# BKN-3.net
KiCad netlist of a schematic drawn in Altium Designer
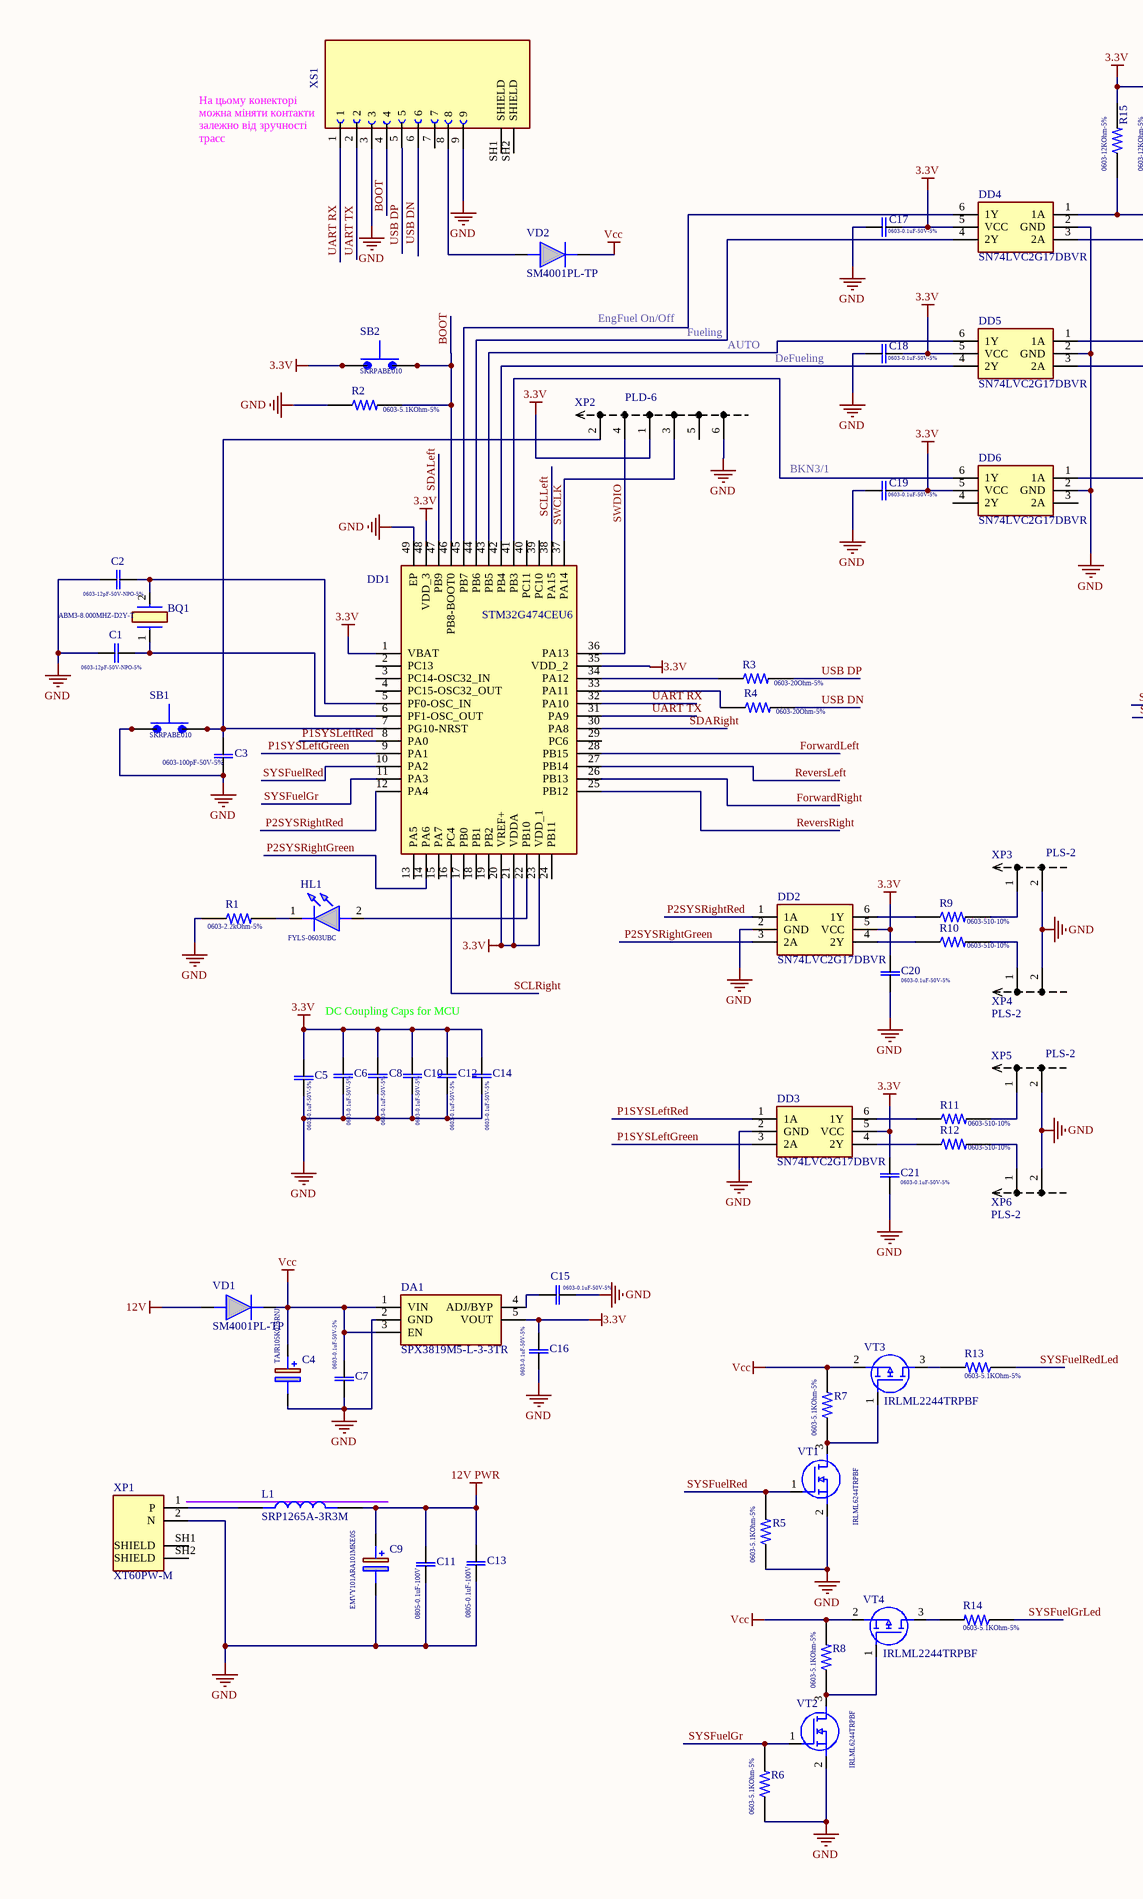
[diagram p0: BKN-3.SchDoc, left]
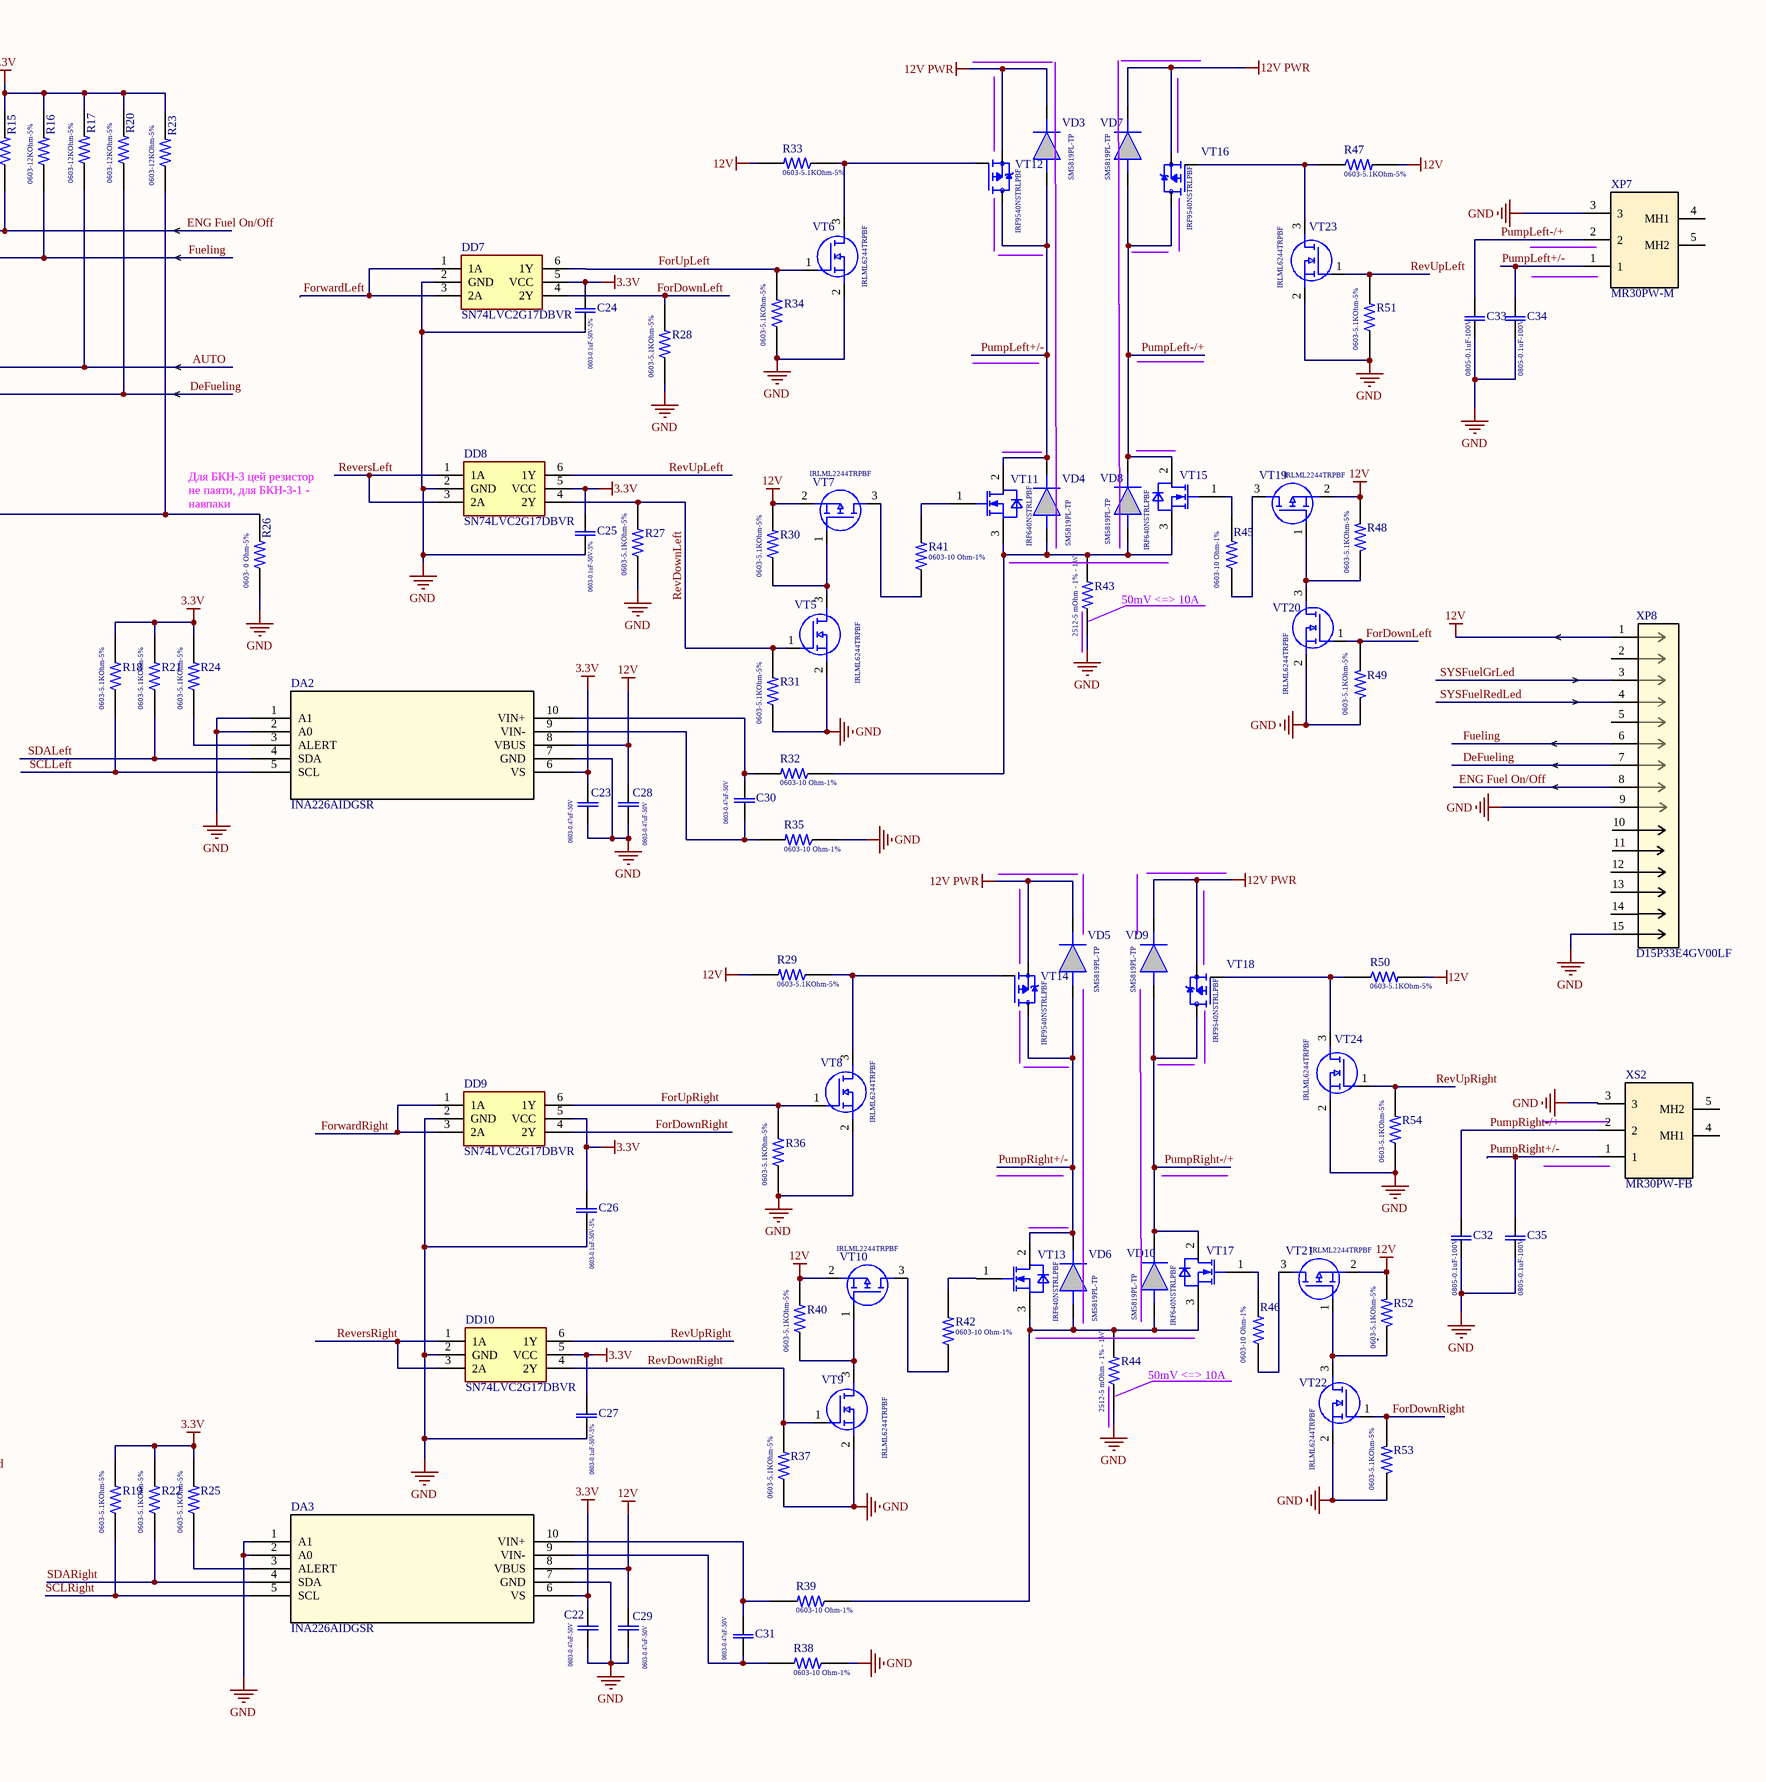
[diagram p1: BKN-3.SchDoc, right]

(export (version "E")
  (design (tool "Eeschema 10.0.6"))
  (components
    (comp (ref "BQ1")
      (value "ABM3-8.000MHZ-D2Y-T")
      (footprint "ABM3-25.000MHz")
      (description "ABM3-8.000MHZ-D2Y-T Кварцевий резонатор Космодром код товару: 00-00066552 Виробник:ABRACON")
      (libsource (lib "Quartz") (part "ABM3-25.000MHz"))
    )
    (comp (ref "C1")
      (value "0603-12pF-50V-NPO-5%")
      (footprint "C0603")
      (libsource (lib "Cap") (part "CAP0603"))
    )
    (comp (ref "C2")
      (value "0603-12pF-50V-NPO-5%")
      (footprint "C0603")
      (libsource (lib "Cap") (part "CAP0603"))
    )
    (comp (ref "C3") (value "0603-100pF-50V-5%") (footprint "C0603") (libsource (lib "Cap") (part "CAP0603")))
    (comp (ref "C4")
      (value "TAJR105K025RNJ")
      (footprint "TAJR105K025RNJ")
      (libsource (lib "CapElectrolite") (part "TAJR105K025RNJ"))
    )
    (comp (ref "C5") (value "0603-0.1uF-50V-5%") (footprint "C0603") (libsource (lib "Cap") (part "CAP0603")))
    (comp (ref "C6") (value "0603-0.1uF-50V-5%") (footprint "C0603") (libsource (lib "Cap") (part "CAP0603")))
    (comp (ref "C7") (value "0603-0.1uF-50V-5%") (footprint "C0603") (libsource (lib "Cap") (part "CAP0603")))
    (comp (ref "C8") (value "0603-0.1uF-50V-5%") (footprint "C0603") (libsource (lib "Cap") (part "CAP0603")))
    (comp (ref "C9")
      (value "EMVY101ARA101MKE0S")
      (footprint "EMVY101ARA101MKE0S")
      (libsource (lib "CapElectrolite") (part "EMVY101ARA101MKE0S"))
    )
    (comp (ref "C10")
      (value "0603-0.1uF-50V-5%")
      (footprint "C0603")
      (libsource (lib "Cap") (part "CAP0603"))
    )
    (comp (ref "C11")
      (value "0805-0.1uF-100V")
      (footprint "Cap0805")
      (libsource (lib "Cap") (part "Cap0805"))
    )
    (comp (ref "C12")
      (value "0603-0.1uF-50V-5%")
      (footprint "C0603")
      (libsource (lib "Cap") (part "CAP0603"))
    )
    (comp (ref "C13")
      (value "0805-0.1uF-100V")
      (footprint "Cap0805")
      (libsource (lib "Cap") (part "Cap0805"))
    )
    (comp (ref "C14")
      (value "0603-0.1uF-50V-5%")
      (footprint "C0603")
      (libsource (lib "Cap") (part "CAP0603"))
    )
    (comp (ref "C15")
      (value "0603-0.1uF-50V-5%")
      (footprint "C0603")
      (libsource (lib "Cap") (part "CAP0603"))
    )
    (comp (ref "C16")
      (value "0603-0.1uF-50V-5%")
      (footprint "C0603")
      (libsource (lib "Cap") (part "CAP0603"))
    )
    (comp (ref "C17")
      (value "0603-0.1uF-50V-5%")
      (footprint "C0603")
      (libsource (lib "Cap") (part "CAP0603"))
    )
    (comp (ref "C18")
      (value "0603-0.1uF-50V-5%")
      (footprint "C0603")
      (libsource (lib "Cap") (part "CAP0603"))
    )
    (comp (ref "C19")
      (value "0603-0.1uF-50V-5%")
      (footprint "C0603")
      (libsource (lib "Cap") (part "CAP0603"))
    )
    (comp (ref "C20")
      (value "0603-0.1uF-50V-5%")
      (footprint "C0603")
      (libsource (lib "Cap") (part "CAP0603"))
    )
    (comp (ref "C21")
      (value "0603-0.1uF-50V-5%")
      (footprint "C0603")
      (libsource (lib "Cap") (part "CAP0603"))
    )
    (comp (ref "C22") (value "0603-0.47uF-50V") (footprint "C0603") (libsource (lib "Cap") (part "CAP0603")))
    (comp (ref "C23") (value "0603-0.47uF-50V") (footprint "C0603") (libsource (lib "Cap") (part "CAP0603")))
    (comp (ref "C24")
      (value "0603-0.1uF-50V-5%")
      (footprint "C0603")
      (libsource (lib "Cap") (part "CAP0603"))
    )
    (comp (ref "C25")
      (value "0603-0.1uF-50V-5%")
      (footprint "C0603")
      (libsource (lib "Cap") (part "CAP0603"))
    )
    (comp (ref "C26")
      (value "0603-0.1uF-50V-5%")
      (footprint "C0603")
      (libsource (lib "Cap") (part "CAP0603"))
    )
    (comp (ref "C27")
      (value "0603-0.1uF-50V-5%")
      (footprint "C0603")
      (libsource (lib "Cap") (part "CAP0603"))
    )
    (comp (ref "C28") (value "0603-0.47uF-50V") (footprint "C0603") (libsource (lib "Cap") (part "CAP0603")))
    (comp (ref "C29") (value "0603-0.47uF-50V") (footprint "C0603") (libsource (lib "Cap") (part "CAP0603")))
    (comp (ref "C30") (value "0603-0.47uF-50V") (footprint "C0603") (libsource (lib "Cap") (part "CAP0603")))
    (comp (ref "C31") (value "0603-0.47uF-50V") (footprint "C0603") (libsource (lib "Cap") (part "CAP0603")))
    (comp (ref "C32")
      (value "0805-0.1uF-100V")
      (footprint "Cap0805")
      (libsource (lib "Cap") (part "Cap0805"))
    )
    (comp (ref "C33")
      (value "0805-0.1uF-100V")
      (footprint "Cap0805")
      (libsource (lib "Cap") (part "Cap0805"))
    )
    (comp (ref "C34")
      (value "0805-0.1uF-100V")
      (footprint "Cap0805")
      (libsource (lib "Cap") (part "Cap0805"))
    )
    (comp (ref "C35")
      (value "0805-0.1uF-100V")
      (footprint "Cap0805")
      (libsource (lib "Cap") (part "Cap0805"))
    )
    (comp (ref "DA1")
      (value "SPX3819M5-L-3-3TR")
      (footprint "SOT95P280x145-5N")
      (libsource (lib "LDO") (part "SPX3819M5-L-3-3TR"))
    )
    (comp (ref "DA2")
      (value "INA226AIDGSR")
      (footprint "INA226AIDGSR")
      (libsource (lib "CurrentMonitor") (part "INA226AIDGSR"))
    )
    (comp (ref "DA3")
      (value "INA226AIDGSR")
      (footprint "INA226AIDGSR")
      (libsource (lib "CurrentMonitor") (part "INA226AIDGSR"))
    )
    (comp (ref "DD1")
      (value "STM32G474CEU6")
      (footprint "QFN50P700X700X60-49N-D")
      (description "STM32G474CEU6\r\nВиробник:\r\nSTMicroelectronics\r\nIC MCU 32BIT 512KB FLSH 48UFQFPN VD MAIS")
      (libsource (lib "STM Controllers") (part "STM32G474CEU6"))
    )
    (comp (ref "DD2")
      (value "SN74LVC2G17DBVR")
      (footprint "SOT95P280x145-6N")
      (libsource (lib "") (part "SN74LVC2G17DBVR_1"))
    )
    (comp (ref "DD3")
      (value "SN74LVC2G17DBVR")
      (footprint "SOT95P280x145-6N")
      (libsource (lib "") (part "SN74LVC2G17DBVR_1"))
    )
    (comp (ref "DD4")
      (value "SN74LVC2G17DBVR")
      (footprint "SOT95P280x145-6N")
      (libsource (lib "Buffer") (part "SN74LVC2G17DBVR"))
    )
    (comp (ref "DD5")
      (value "SN74LVC2G17DBVR")
      (footprint "SOT95P280x145-6N")
      (libsource (lib "Buffer") (part "SN74LVC2G17DBVR"))
    )
    (comp (ref "DD6")
      (value "SN74LVC2G17DBVR")
      (footprint "SOT95P280x145-6N")
      (libsource (lib "Buffer") (part "SN74LVC2G17DBVR"))
    )
    (comp (ref "DD7")
      (value "SN74LVC2G17DBVR")
      (footprint "SOT95P280x145-6N")
      (libsource (lib "") (part "SN74LVC2G17DBVR_1"))
    )
    (comp (ref "DD8")
      (value "SN74LVC2G17DBVR")
      (footprint "SOT95P280x145-6N")
      (libsource (lib "") (part "SN74LVC2G17DBVR_1"))
    )
    (comp (ref "DD9")
      (value "SN74LVC2G17DBVR")
      (footprint "SOT95P280x145-6N")
      (libsource (lib "") (part "SN74LVC2G17DBVR_1"))
    )
    (comp (ref "DD10")
      (value "SN74LVC2G17DBVR")
      (footprint "SOT95P280x145-6N")
      (libsource (lib "") (part "SN74LVC2G17DBVR_1"))
    )
    (comp (ref "HL1") (value "FYLS-0603UBC") (footprint "LED0603") (libsource (lib "LEDs") (part "LED0603")))
    (comp (ref "L1")
      (value "SRP1265A-3R3M")
      (footprint "SRP1265A-3R3M")
      (libsource (lib "Inductance") (part "SRP1265A-3R3M"))
    )
    (comp (ref "R1")
      (value "0603-2.2kOhm-5%")
      (footprint "Res0603")
      (libsource (lib "Resisitor") (part "Res0603"))
    )
    (comp (ref "R2")
      (value "0603-5.1KOhm-5%")
      (footprint "Res0603")
      (libsource (lib "Resisitor") (part "Res0603"))
    )
    (comp (ref "R3")
      (value "0603-20Ohm-5%")
      (footprint "Res0603")
      (libsource (lib "Resisitor") (part "Res0603"))
    )
    (comp (ref "R4")
      (value "0603-20Ohm-5%")
      (footprint "Res0603")
      (libsource (lib "Resisitor") (part "Res0603"))
    )
    (comp (ref "R5")
      (value "0603-5.1KOhm-5%")
      (footprint "Res0603")
      (libsource (lib "Resisitor") (part "Res0603"))
    )
    (comp (ref "R6")
      (value "0603-5.1KOhm-5%")
      (footprint "Res0603")
      (libsource (lib "Resisitor") (part "Res0603"))
    )
    (comp (ref "R7")
      (value "0603-5.1KOhm-5%")
      (footprint "Res0603")
      (libsource (lib "Resisitor") (part "Res0603"))
    )
    (comp (ref "R8")
      (value "0603-5.1KOhm-5%")
      (footprint "Res0603")
      (libsource (lib "Resisitor") (part "Res0603"))
    )
    (comp (ref "R9")
      (value "0603-510-10%")
      (footprint "Res0603")
      (libsource (lib "Resisitor") (part "Res0603"))
    )
    (comp (ref "R10")
      (value "0603-510-10%")
      (footprint "Res0603")
      (libsource (lib "Resisitor") (part "Res0603"))
    )
    (comp (ref "R11")
      (value "0603-510-10%")
      (footprint "Res0603")
      (libsource (lib "Resisitor") (part "Res0603"))
    )
    (comp (ref "R12")
      (value "0603-510-10%")
      (footprint "Res0603")
      (libsource (lib "Resisitor") (part "Res0603"))
    )
    (comp (ref "R13")
      (value "0603-5.1KOhm-5%")
      (footprint "Res0603")
      (libsource (lib "Resisitor") (part "Res0603"))
    )
    (comp (ref "R14")
      (value "0603-5.1KOhm-5%")
      (footprint "Res0603")
      (libsource (lib "Resisitor") (part "Res0603"))
    )
    (comp (ref "R15")
      (value "0603-12KOhm-5%")
      (footprint "Res0603")
      (libsource (lib "Resisitor") (part "Res0603"))
    )
    (comp (ref "R16")
      (value "0603-12KOhm-5%")
      (footprint "Res0603")
      (libsource (lib "Resisitor") (part "Res0603"))
    )
    (comp (ref "R17")
      (value "0603-12KOhm-5%")
      (footprint "Res0603")
      (libsource (lib "Resisitor") (part "Res0603"))
    )
    (comp (ref "R18")
      (value "0603-5.1KOhm-5%")
      (footprint "Res0603")
      (libsource (lib "Resisitor") (part "Res0603"))
    )
    (comp (ref "R19")
      (value "0603-5.1KOhm-5%")
      (footprint "Res0603")
      (libsource (lib "Resisitor") (part "Res0603"))
    )
    (comp (ref "R20")
      (value "0603-12KOhm-5%")
      (footprint "Res0603")
      (libsource (lib "Resisitor") (part "Res0603"))
    )
    (comp (ref "R21")
      (value "0603-5.1KOhm-5%")
      (footprint "Res0603")
      (libsource (lib "Resisitor") (part "Res0603"))
    )
    (comp (ref "R22")
      (value "0603-5.1KOhm-5%")
      (footprint "Res0603")
      (libsource (lib "Resisitor") (part "Res0603"))
    )
    (comp (ref "R23")
      (value "0603-12KOhm-5%")
      (footprint "Res0603")
      (libsource (lib "Resisitor") (part "Res0603"))
    )
    (comp (ref "R24")
      (value "0603-5.1KOhm-5%")
      (footprint "Res0603")
      (libsource (lib "Resisitor") (part "Res0603"))
    )
    (comp (ref "R25")
      (value "0603-5.1KOhm-5%")
      (footprint "Res0603")
      (libsource (lib "Resisitor") (part "Res0603"))
    )
    (comp (ref "R26")
      (value "0603- 0 Ohm-5%")
      (footprint "Res0603")
      (libsource (lib "Resisitor") (part "Res0603"))
    )
    (comp (ref "R27")
      (value "0603-5.1KOhm-5%")
      (footprint "Res0603")
      (libsource (lib "Resisitor") (part "Res0603"))
    )
    (comp (ref "R28")
      (value "0603-5.1KOhm-5%")
      (footprint "Res0603")
      (libsource (lib "Resisitor") (part "Res0603"))
    )
    (comp (ref "R29")
      (value "0603-5.1KOhm-5%")
      (footprint "Res0603")
      (libsource (lib "Resisitor") (part "Res0603"))
    )
    (comp (ref "R30")
      (value "0603-5.1KOhm-5%")
      (footprint "Res0603")
      (libsource (lib "Resisitor") (part "Res0603"))
    )
    (comp (ref "R31")
      (value "0603-5.1KOhm-5%")
      (footprint "Res0603")
      (libsource (lib "Resisitor") (part "Res0603"))
    )
    (comp (ref "R32")
      (value "0603-10 Ohm-1%")
      (footprint "Res0603")
      (libsource (lib "Resisitor") (part "Res0603"))
    )
    (comp (ref "R33")
      (value "0603-5.1KOhm-5%")
      (footprint "Res0603")
      (libsource (lib "Resisitor") (part "Res0603"))
    )
    (comp (ref "R34")
      (value "0603-5.1KOhm-5%")
      (footprint "Res0603")
      (libsource (lib "Resisitor") (part "Res0603"))
    )
    (comp (ref "R35")
      (value "0603-10 Ohm-1%")
      (footprint "Res0603")
      (libsource (lib "Resisitor") (part "Res0603"))
    )
    (comp (ref "R36")
      (value "0603-5.1KOhm-5%")
      (footprint "Res0603")
      (libsource (lib "Resisitor") (part "Res0603"))
    )
    (comp (ref "R37")
      (value "0603-5.1KOhm-5%")
      (footprint "Res0603")
      (libsource (lib "Resisitor") (part "Res0603"))
    )
    (comp (ref "R38")
      (value "0603-10 Ohm-1%")
      (footprint "Res0603")
      (libsource (lib "Resisitor") (part "Res0603"))
    )
    (comp (ref "R39")
      (value "0603-10 Ohm-1%")
      (footprint "Res0603")
      (libsource (lib "Resisitor") (part "Res0603"))
    )
    (comp (ref "R40")
      (value "0603-5.1KOhm-5%")
      (footprint "Res0603")
      (libsource (lib "Resisitor") (part "Res0603"))
    )
    (comp (ref "R41")
      (value "0603-10 Ohm-1%")
      (footprint "Res0603")
      (libsource (lib "Resisitor") (part "Res0603"))
    )
    (comp (ref "R42")
      (value "0603-10 Ohm-1%")
      (footprint "Res0603")
      (libsource (lib "Resisitor") (part "Res0603"))
    )
    (comp (ref "R43")
      (value "2512-5 mOhm - 1% - 1W")
      (footprint "Res2512")
      (libsource (lib "Resisitor") (part "Res2512"))
    )
    (comp (ref "R44")
      (value "2512-5 mOhm - 1% - 1W")
      (footprint "Res2512")
      (libsource (lib "Resisitor") (part "Res2512"))
    )
    (comp (ref "R45")
      (value "0603-10 Ohm-1%")
      (footprint "Res0603")
      (libsource (lib "Resisitor") (part "Res0603"))
    )
    (comp (ref "R46")
      (value "0603-10 Ohm-1%")
      (footprint "Res0603")
      (libsource (lib "Resisitor") (part "Res0603"))
    )
    (comp (ref "R47")
      (value "0603-5.1KOhm-5%")
      (footprint "Res0603")
      (libsource (lib "Resisitor") (part "Res0603"))
    )
    (comp (ref "R48")
      (value "0603-5.1KOhm-5%")
      (footprint "Res0603")
      (libsource (lib "Resisitor") (part "Res0603"))
    )
    (comp (ref "R49")
      (value "0603-5.1KOhm-5%")
      (footprint "Res0603")
      (libsource (lib "Resisitor") (part "Res0603"))
    )
    (comp (ref "R50")
      (value "0603-5.1KOhm-5%")
      (footprint "Res0603")
      (libsource (lib "Resisitor") (part "Res0603"))
    )
    (comp (ref "R51")
      (value "0603-5.1KOhm-5%")
      (footprint "Res0603")
      (libsource (lib "Resisitor") (part "Res0603"))
    )
    (comp (ref "R52")
      (value "0603-5.1KOhm-5%")
      (footprint "Res0603")
      (libsource (lib "Resisitor") (part "Res0603"))
    )
    (comp (ref "R53")
      (value "0603-5.1KOhm-5%")
      (footprint "Res0603")
      (libsource (lib "Resisitor") (part "Res0603"))
    )
    (comp (ref "R54")
      (value "0603-5.1KOhm-5%")
      (footprint "Res0603")
      (libsource (lib "Resisitor") (part "Res0603"))
    )
    (comp (ref "SB1")
      (value "SKRPABE010")
      (footprint "SKRPABE010")
      (libsource (lib "Button") (part "SKRPABE010"))
    )
    (comp (ref "SB2")
      (value "SKRPABE010")
      (footprint "SKRPABE010")
      (libsource (lib "Button") (part "SKRPABE010"))
    )
    (comp (ref "VD1")
      (value "SM4001PL-TP")
      (footprint "SODFL3716X120N")
      (description "Производитель: MCC\r\nТип корпуса: SOD-123\r\nКосмодром код товара: 00-00072425")
      (libsource (lib "Diodes") (part "SM4001PL-TP"))
    )
    (comp (ref "VD2")
      (value "SM4001PL-TP")
      (footprint "SODFL3716X120N")
      (libsource (lib "Diodes") (part "SM4001PL-TP"))
    )
    (comp (ref "VD3")
      (value "SM5819PL-TP")
      (footprint "SM5819PL-TP (SOD123)")
      (description "SM5819PL\r\nImrad Артикул: 195754\r\nПроизводитель: MCC\r\nКорпус: SOD-123")
      (libsource (lib "Diodes") (part "SM5819PL-TP"))
    )
    (comp (ref "VD4")
      (value "SM5819PL-TP")
      (footprint "SM5819PL-TP (SOD123)")
      (description "SM5819PL\r\nImrad Артикул: 195754\r\nПроизводитель: MCC\r\nКорпус: SOD-123")
      (libsource (lib "Diodes") (part "SM5819PL-TP"))
    )
    (comp (ref "VD5")
      (value "SM5819PL-TP")
      (footprint "SM5819PL-TP (SOD123)")
      (description "SM5819PL\r\nImrad Артикул: 195754\r\nПроизводитель: MCC\r\nКорпус: SOD-123")
      (libsource (lib "Diodes") (part "SM5819PL-TP"))
    )
    (comp (ref "VD6")
      (value "SM5819PL-TP")
      (footprint "SM5819PL-TP (SOD123)")
      (description "SM5819PL\r\nImrad Артикул: 195754\r\nПроизводитель: MCC\r\nКорпус: SOD-123")
      (libsource (lib "Diodes") (part "SM5819PL-TP"))
    )
    (comp (ref "VD7")
      (value "SM5819PL-TP")
      (footprint "SM5819PL-TP (SOD123)")
      (description "SM5819PL\r\nImrad Артикул: 195754\r\nПроизводитель: MCC\r\nКорпус: SOD-123")
      (libsource (lib "Diodes") (part "SM5819PL-TP"))
    )
    (comp (ref "VD8")
      (value "SM5819PL-TP")
      (footprint "SM5819PL-TP (SOD123)")
      (description "SM5819PL\r\nImrad Артикул: 195754\r\nПроизводитель: MCC\r\nКорпус: SOD-123")
      (libsource (lib "Diodes") (part "SM5819PL-TP"))
    )
    (comp (ref "VD9")
      (value "SM5819PL-TP")
      (footprint "SM5819PL-TP (SOD123)")
      (description "SM5819PL\r\nImrad Артикул: 195754\r\nПроизводитель: MCC\r\nКорпус: SOD-123")
      (libsource (lib "Diodes") (part "SM5819PL-TP"))
    )
    (comp (ref "VD10")
      (value "SM5819PL-TP")
      (footprint "SM5819PL-TP (SOD123)")
      (description "SM5819PL\r\nImrad Артикул: 195754\r\nПроизводитель: MCC\r\nКорпус: SOD-123")
      (libsource (lib "Diodes") (part "SM5819PL-TP"))
    )
    (comp (ref "VT1")
      (value "IRLML6244TRPBF")
      (footprint "SOT95P230x110-3N")
      (libsource (lib "NFET") (part "IRLML6244"))
    )
    (comp (ref "VT2")
      (value "IRLML6244TRPBF")
      (footprint "SOT95P230x110-3N")
      (libsource (lib "NFET") (part "IRLML6244"))
    )
    (comp (ref "VT3")
      (value "IRLML2244TRPBF")
      (footprint "SOT95P237x112-3N")
      (libsource (lib "PFET") (part "IRLML2244"))
    )
    (comp (ref "VT4")
      (value "IRLML2244TRPBF")
      (footprint "SOT95P237x112-3N")
      (libsource (lib "PFET") (part "IRLML2244"))
    )
    (comp (ref "VT5")
      (value "IRLML6244TRPBF")
      (footprint "SOT95P230x110-3N")
      (libsource (lib "NFET") (part "IRLML6244"))
    )
    (comp (ref "VT6")
      (value "IRLML6244TRPBF")
      (footprint "SOT95P230x110-3N")
      (libsource (lib "NFET") (part "IRLML6244"))
    )
    (comp (ref "VT7")
      (value "IRLML2244TRPBF")
      (footprint "SOT95P237x112-3N")
      (libsource (lib "PFET") (part "IRLML2244"))
    )
    (comp (ref "VT8")
      (value "IRLML6244TRPBF")
      (footprint "SOT95P230x110-3N")
      (libsource (lib "NFET") (part "IRLML6244"))
    )
    (comp (ref "VT9")
      (value "IRLML6244TRPBF")
      (footprint "SOT95P230x110-3N")
      (libsource (lib "NFET") (part "IRLML6244"))
    )
    (comp (ref "VT10")
      (value "IRLML2244TRPBF")
      (footprint "SOT95P237x112-3N")
      (libsource (lib "PFET") (part "IRLML2244"))
    )
    (comp (ref "VT11")
      (value "IRF640NSTRLPBF")
      (footprint "IRF640NSTRLPBF")
      (libsource (lib "NFET") (part "IRF640NSTRLPBF"))
    )
    (comp (ref "VT12")
      (value "IRF9540NSTRLPBF")
      (footprint "IRF9540NSTRLPBF")
      (libsource (lib "PFET") (part "IRF9540NSTRLPBF"))
    )
    (comp (ref "VT13")
      (value "IRF640NSTRLPBF")
      (footprint "IRF640NSTRLPBF")
      (libsource (lib "NFET") (part "IRF640NSTRLPBF"))
    )
    (comp (ref "VT14")
      (value "IRF9540NSTRLPBF")
      (footprint "IRF9540NSTRLPBF")
      (libsource (lib "PFET") (part "IRF9540NSTRLPBF"))
    )
    (comp (ref "VT15")
      (value "IRF640NSTRLPBF")
      (footprint "IRF640NSTRLPBF")
      (libsource (lib "NFET") (part "IRF640NSTRLPBF"))
    )
    (comp (ref "VT16")
      (value "IRF9540NSTRLPBF")
      (footprint "IRF9540NSTRLPBF")
      (libsource (lib "PFET") (part "IRF9540NSTRLPBF"))
    )
    (comp (ref "VT17")
      (value "IRF640NSTRLPBF")
      (footprint "IRF640NSTRLPBF")
      (libsource (lib "NFET") (part "IRF640NSTRLPBF"))
    )
    (comp (ref "VT18")
      (value "IRF9540NSTRLPBF")
      (footprint "IRF9540NSTRLPBF")
      (libsource (lib "PFET") (part "IRF9540NSTRLPBF"))
    )
    (comp (ref "VT19")
      (value "IRLML2244TRPBF")
      (footprint "SOT95P237x112-3N")
      (libsource (lib "PFET") (part "IRLML2244"))
    )
    (comp (ref "VT20")
      (value "IRLML6244TRPBF")
      (footprint "SOT95P230x110-3N")
      (libsource (lib "NFET") (part "IRLML6244"))
    )
    (comp (ref "VT21")
      (value "IRLML2244TRPBF")
      (footprint "SOT95P237x112-3N")
      (libsource (lib "PFET") (part "IRLML2244"))
    )
    (comp (ref "VT22")
      (value "IRLML6244TRPBF")
      (footprint "SOT95P230x110-3N")
      (libsource (lib "NFET") (part "IRLML6244"))
    )
    (comp (ref "VT23")
      (value "IRLML6244TRPBF")
      (footprint "SOT95P230x110-3N")
      (libsource (lib "NFET") (part "IRLML6244"))
    )
    (comp (ref "VT24")
      (value "IRLML6244TRPBF")
      (footprint "SOT95P230x110-3N")
      (libsource (lib "NFET") (part "IRLML6244"))
    )
    (comp (ref "XP1") (value "XT60PW-M") (footprint "XT60PW-M") (libsource (lib "AMASS") (part "XT60PW-M")))
    (comp (ref "XP2") (value "PLD-6") (footprint "PLD-6") (libsource (lib "PLS_PLD") (part "PLD-6")))
    (comp (ref "XP3") (value "PLS-2") (footprint "PLS-2") (libsource (lib "PLS_PLD") (part "PLS-2")))
    (comp (ref "XP4") (value "PLS-2") (footprint "PLS-2") (libsource (lib "PLS_PLD") (part "PLS-2")))
    (comp (ref "XP5") (value "PLS-2") (footprint "PLS-2") (libsource (lib "PLS_PLD") (part "PLS-2")))
    (comp (ref "XP6") (value "PLS-2") (footprint "PLS-2") (libsource (lib "PLS_PLD") (part "PLS-2")))
    (comp (ref "XP7")
      (value "MR30PW-M")
      (footprint "MR30PW-M")
      (description "MR30PW-M\r\nImrad Артикул: 393200\r\nВиробник: AMASS\r\nНаявність: В наявності")
      (libsource (lib "AMASS") (part "MR30PW-M"))
    )
    (comp (ref "XP8")
      (value "D15P33E4GV00LF")
      (footprint "D15P33E4GV00LF (Amphenol)")
      (description "DRB-15MA\r\nImrad Артикул: 201593\r\nНазва виробника: DS1037-15MNAKT74-0CC\r\nВиробник: CONNFLY")
      (libsource (lib "DSUB") (part "D15P33E4GV00LF"))
    )
    (comp (ref "XS1")
      (value "AMPHENOL_LD09S33E4GV00LF (DB9 ThrHole Right Receptacle )")
      (footprint "AMPHENOL_LD09S33E4GV00LF (9pin receptacle)")
      (libsource (lib "DSUB") (part "AMPHENOL_LD09S33E4GV00LF (DB9 ThrHole Right Receptacle )"))
    )
    (comp (ref "XS2")
      (value "MR30PW-FB")
      (footprint "MR30PW-FB")
      (description "MR30PW-FB\r\nImrad Артикул: 393199\r\nВиробник: AMASS\r\nНаявність: В наявності")
      (libsource (lib "AMASS") (part "MR30PW-FB"))
    )
  )
  (nets
    (net (code "1") (name "/AUTO") (class "Default")
      (node (ref "DD5") (pin "1") (pinfunction "1A_1") (pintype "passive"))
      (node (ref "R17") (pin "1") (pinfunction "1_1") (pintype "passive"))
    )
    (net (code "2") (name "/BOOT") (class "Default")
      (node (ref "DD1") (pin "46") (pinfunction "PB8-BOOT0_46") (pintype "passive"))
      (node (ref "R2") (pin "2") (pinfunction "2_2") (pintype "passive"))
      (node (ref "SB2") (pin "3") (pinfunction "2_3") (pintype "passive"))
      (node (ref "SB2") (pin "4") (pinfunction "2_4") (pintype "passive"))
      (node (ref "XS1") (pin "4") (pinfunction "4_4") (pintype "passive"))
    )
    (net (code "3") (name "/DeFueling") (class "Default")
      (node (ref "DD5") (pin "3") (pinfunction "2A_3") (pintype "passive"))
      (node (ref "R20") (pin "1") (pinfunction "1_1") (pintype "passive"))
      (node (ref "XP8") (pin "7") (pinfunction "7_7") (pintype "passive"))
    )
    (net (code "4") (name "/ENG Fuel On{slash}Off") (class "Default")
      (node (ref "DD4") (pin "1") (pinfunction "1A_1") (pintype "passive"))
      (node (ref "R15") (pin "1") (pinfunction "1_1") (pintype "passive"))
      (node (ref "XP8") (pin "8") (pinfunction "8_8") (pintype "passive"))
    )
    (net (code "5") (name "/ForDownLeft") (class "Default")
      (node (ref "DD7") (pin "4") (pinfunction "2Y_4") (pintype "passive"))
      (node (ref "R28") (pin "2") (pinfunction "2_2") (pintype "passive"))
      (node (ref "R49") (pin "2") (pinfunction "2_2") (pintype "passive"))
      (node (ref "VT20") (pin "1") (pinfunction "G_1") (pintype "passive"))
    )
    (net (code "6") (name "/ForDownRight") (class "Default")
      (node (ref "DD9") (pin "4") (pinfunction "2Y_4") (pintype "passive"))
      (node (ref "R53") (pin "2") (pinfunction "2_2") (pintype "passive"))
      (node (ref "VT22") (pin "1") (pinfunction "G_1") (pintype "passive"))
    )
    (net (code "8") (name "/ForUpLeft") (class "Default")
      (node (ref "DD7") (pin "6") (pinfunction "1Y_6") (pintype "passive"))
      (node (ref "R34") (pin "2") (pinfunction "2_2") (pintype "passive"))
      (node (ref "VT6") (pin "1") (pinfunction "G_1") (pintype "passive"))
    )
    (net (code "9") (name "/ForUpRight") (class "Default")
      (node (ref "DD9") (pin "6") (pinfunction "1Y_6") (pintype "passive"))
      (node (ref "R36") (pin "2") (pinfunction "2_2") (pintype "passive"))
      (node (ref "VT8") (pin "1") (pinfunction "G_1") (pintype "passive"))
    )
    (net (code "10") (name "/ForwardLeft") (class "Default")
      (node (ref "DD1") (pin "28") (pinfunction "PB15_28") (pintype "passive"))
      (node (ref "DD7") (pin "1") (pinfunction "1A_1") (pintype "passive"))
      (node (ref "DD7") (pin "3") (pinfunction "2A_3") (pintype "passive"))
    )
    (net (code "11") (name "/ForwardRight") (class "Default")
      (node (ref "DD1") (pin "26") (pinfunction "PB13_26") (pintype "passive"))
      (node (ref "DD9") (pin "1") (pinfunction "1A_1") (pintype "passive"))
      (node (ref "DD9") (pin "3") (pinfunction "2A_3") (pintype "passive"))
    )
    (net (code "12") (name "/Fueling") (class "Default")
      (node (ref "DD4") (pin "3") (pinfunction "2A_3") (pintype "passive"))
      (node (ref "R16") (pin "1") (pinfunction "1_1") (pintype "passive"))
      (node (ref "XP8") (pin "6") (pinfunction "6_6") (pintype "passive"))
    )
    (net (code "13") (name "/P1SYSLeftGreen") (class "Default")
      (node (ref "DD1") (pin "9") (pinfunction "PA1_9") (pintype "passive"))
      (node (ref "DD3") (pin "3") (pinfunction "2A_3") (pintype "passive"))
    )
    (net (code "14") (name "/P1SYSLeftRed") (class "Default")
      (node (ref "DD1") (pin "8") (pinfunction "PA0_8") (pintype "passive"))
      (node (ref "DD3") (pin "1") (pinfunction "1A_1") (pintype "passive"))
    )
    (net (code "15") (name "/P2SYSRightGreen") (class "Default")
      (node (ref "DD1") (pin "14") (pinfunction "PA6_14") (pintype "passive"))
      (node (ref "DD2") (pin "3") (pinfunction "2A_3") (pintype "passive"))
    )
    (net (code "16") (name "/P2SYSRightRed") (class "Default")
      (node (ref "DD1") (pin "12") (pinfunction "PA4_12") (pintype "passive"))
      (node (ref "DD2") (pin "1") (pinfunction "1A_1") (pintype "passive"))
    )
    (net (code "17") (name "/PumpLeft+{slash}-") (class "Default")
      (node (ref "C34") (pin "1") (pinfunction "1_1") (pintype "passive"))
      (node (ref "VD3") (pin "2") (pinfunction "A_2") (pintype "passive"))
      (node (ref "VD4") (pin "1") (pinfunction "K_1") (pintype "passive"))
      (node (ref "VT11") (pin "2") (pinfunction "2,4_2") (pintype "passive"))
      (node (ref "VT12") (pin "4") (pinfunction "D_4") (pintype "passive"))
      (node (ref "XP7") (pin "1") (pinfunction "1_1") (pintype "passive"))
    )
    (net (code "18") (name "/PumpLeft-{slash}+") (class "Default")
      (node (ref "C33") (pin "1") (pinfunction "1_1") (pintype "passive"))
      (node (ref "VD7") (pin "2") (pinfunction "A_2") (pintype "passive"))
      (node (ref "VD8") (pin "1") (pinfunction "K_1") (pintype "passive"))
      (node (ref "VT15") (pin "2") (pinfunction "2,4_2") (pintype "passive"))
      (node (ref "VT16") (pin "4") (pinfunction "D_4") (pintype "passive"))
      (node (ref "XP7") (pin "2") (pinfunction "2_2") (pintype "passive"))
    )
    (net (code "19") (name "/PumpRight+{slash}-") (class "Default")
      (node (ref "C35") (pin "1") (pinfunction "1_1") (pintype "passive"))
      (node (ref "VD5") (pin "2") (pinfunction "A_2") (pintype "passive"))
      (node (ref "VD6") (pin "1") (pinfunction "K_1") (pintype "passive"))
      (node (ref "VT13") (pin "2") (pinfunction "2,4_2") (pintype "passive"))
      (node (ref "VT14") (pin "4") (pinfunction "D_4") (pintype "passive"))
      (node (ref "XS2") (pin "1") (pinfunction "1_1") (pintype "passive"))
    )
    (net (code "20") (name "/PumpRight-{slash}+") (class "Default")
      (node (ref "C32") (pin "1") (pinfunction "1_1") (pintype "passive"))
      (node (ref "VD10") (pin "1") (pinfunction "K_1") (pintype "passive"))
      (node (ref "VD9") (pin "2") (pinfunction "A_2") (pintype "passive"))
      (node (ref "VT17") (pin "2") (pinfunction "2,4_2") (pintype "passive"))
      (node (ref "VT18") (pin "4") (pinfunction "D_4") (pintype "passive"))
      (node (ref "XS2") (pin "2") (pinfunction "2_2") (pintype "passive"))
    )
    (net (code "21") (name "/RevDownLeft") (class "Default")
      (node (ref "DD8") (pin "4") (pinfunction "2Y_4") (pintype "passive"))
      (node (ref "R27") (pin "2") (pinfunction "2_2") (pintype "passive"))
      (node (ref "R31") (pin "2") (pinfunction "2_2") (pintype "passive"))
      (node (ref "VT5") (pin "1") (pinfunction "G_1") (pintype "passive"))
    )
    (net (code "22") (name "/RevDownRight") (class "Default")
      (node (ref "DD10") (pin "4") (pinfunction "2Y_4") (pintype "passive"))
      (node (ref "R37") (pin "2") (pinfunction "2_2") (pintype "passive"))
      (node (ref "VT9") (pin "1") (pinfunction "G_1") (pintype "passive"))
    )
    (net (code "23") (name "/RevUpLeft") (class "Default")
      (node (ref "DD8") (pin "6") (pinfunction "1Y_6") (pintype "passive"))
      (node (ref "R51") (pin "2") (pinfunction "2_2") (pintype "passive"))
      (node (ref "VT23") (pin "1") (pinfunction "G_1") (pintype "passive"))
    )
    (net (code "24") (name "/RevUpRight") (class "Default")
      (node (ref "DD10") (pin "6") (pinfunction "1Y_6") (pintype "passive"))
      (node (ref "R54") (pin "2") (pinfunction "2_2") (pintype "passive"))
      (node (ref "VT24") (pin "1") (pinfunction "G_1") (pintype "passive"))
    )
    (net (code "25") (name "/ReversLeft") (class "Default")
      (node (ref "DD1") (pin "27") (pinfunction "PB14_27") (pintype "passive"))
      (node (ref "DD8") (pin "1") (pinfunction "1A_1") (pintype "passive"))
      (node (ref "DD8") (pin "3") (pinfunction "2A_3") (pintype "passive"))
    )
    (net (code "26") (name "/ReversRight") (class "Default")
      (node (ref "DD1") (pin "25") (pinfunction "PB12_25") (pintype "passive"))
      (node (ref "DD10") (pin "1") (pinfunction "1A_1") (pintype "passive"))
      (node (ref "DD10") (pin "3") (pinfunction "2A_3") (pintype "passive"))
    )
    (net (code "27") (name "/SCLLeft") (class "Default")
      (node (ref "DA2") (pin "5") (pinfunction "SCL_5") (pintype "passive"))
      (node (ref "DD1") (pin "38") (pinfunction "PA15_38") (pintype "passive"))
      (node (ref "R18") (pin "1") (pinfunction "1_1") (pintype "passive"))
    )
    (net (code "28") (name "/SCLRight") (class "Default")
      (node (ref "DA3") (pin "5") (pinfunction "SCL_5") (pintype "passive"))
      (node (ref "DD1") (pin "16") (pinfunction "PC4_16") (pintype "passive"))
      (node (ref "R19") (pin "1") (pinfunction "1_1") (pintype "passive"))
    )
    (net (code "29") (name "/SDALeft") (class "Default")
      (node (ref "DA2") (pin "4") (pinfunction "SDA_4") (pintype "passive"))
      (node (ref "DD1") (pin "47") (pinfunction "PB9_47") (pintype "passive"))
      (node (ref "R21") (pin "1") (pinfunction "1_1") (pintype "passive"))
    )
    (net (code "30") (name "/SDARight") (class "Default")
      (node (ref "DA3") (pin "4") (pinfunction "SDA_4") (pintype "passive"))
      (node (ref "DD1") (pin "30") (pinfunction "PA8_30") (pintype "passive"))
      (node (ref "R22") (pin "1") (pinfunction "1_1") (pintype "passive"))
    )
    (net (code "31") (name "/SYSFuelGr") (class "Default")
      (node (ref "DD1") (pin "11") (pinfunction "PA3_11") (pintype "passive"))
      (node (ref "R6") (pin "2") (pinfunction "2_2") (pintype "passive"))
      (node (ref "VT2") (pin "1") (pinfunction "G_1") (pintype "passive"))
    )
    (net (code "32") (name "/SYSFuelGrLed") (class "Default")
      (node (ref "R14") (pin "1") (pinfunction "1_1") (pintype "passive"))
      (node (ref "XP8") (pin "3") (pinfunction "3_3") (pintype "passive"))
    )
    (net (code "33") (name "/SYSFuelRed") (class "Default")
      (node (ref "DD1") (pin "10") (pinfunction "PA2_10") (pintype "passive"))
      (node (ref "R5") (pin "2") (pinfunction "2_2") (pintype "passive"))
      (node (ref "VT1") (pin "1") (pinfunction "G_1") (pintype "passive"))
    )
    (net (code "34") (name "/SYSFuelRedLed") (class "Default")
      (node (ref "R13") (pin "1") (pinfunction "1_1") (pintype "passive"))
      (node (ref "XP8") (pin "4") (pinfunction "4_4") (pintype "passive"))
    )
    (net (code "35") (name "/UART RX") (class "Default")
      (node (ref "DD1") (pin "32") (pinfunction "PA10_32") (pintype "passive"))
      (node (ref "XS1") (pin "1") (pinfunction "1_1") (pintype "passive"))
    )
    (net (code "36") (name "/UART TX") (class "Default")
      (node (ref "DD1") (pin "31") (pinfunction "PA9_31") (pintype "passive"))
      (node (ref "XS1") (pin "2") (pinfunction "2_2") (pintype "passive"))
    )
    (net (code "37") (name "/USB DN") (class "Default")
      (node (ref "R4") (pin "2") (pinfunction "2_2") (pintype "passive"))
      (node (ref "XS1") (pin "6") (pinfunction "6_6") (pintype "passive"))
    )
    (net (code "38") (name "/USB DP") (class "Default")
      (node (ref "R3") (pin "2") (pinfunction "2_2") (pintype "passive"))
      (node (ref "XS1") (pin "5") (pinfunction "5_5") (pintype "passive"))
    )
    (net (code "39") (name "3.3V") (class "Default")
      (node (ref "C10") (pin "2") (pinfunction "2_2") (pintype "passive"))
      (node (ref "C12") (pin "2") (pinfunction "2_2") (pintype "passive"))
      (node (ref "C14") (pin "2") (pinfunction "2_2") (pintype "passive"))
      (node (ref "C16") (pin "2") (pinfunction "2_2") (pintype "passive"))
      (node (ref "C17") (pin "1") (pinfunction "1_1") (pintype "passive"))
      (node (ref "C18") (pin "1") (pinfunction "1_1") (pintype "passive"))
      (node (ref "C19") (pin "1") (pinfunction "1_1") (pintype "passive"))
      (node (ref "C20") (pin "1") (pinfunction "1_1") (pintype "passive"))
      (node (ref "C21") (pin "1") (pinfunction "1_1") (pintype "passive"))
      (node (ref "C22") (pin "2") (pinfunction "2_2") (pintype "passive"))
      (node (ref "C23") (pin "2") (pinfunction "2_2") (pintype "passive"))
      (node (ref "C24") (pin "2") (pinfunction "2_2") (pintype "passive"))
      (node (ref "C25") (pin "2") (pinfunction "2_2") (pintype "passive"))
      (node (ref "C26") (pin "2") (pinfunction "2_2") (pintype "passive"))
      (node (ref "C27") (pin "2") (pinfunction "2_2") (pintype "passive"))
      (node (ref "C5") (pin "2") (pinfunction "2_2") (pintype "passive"))
      (node (ref "C6") (pin "2") (pinfunction "2_2") (pintype "passive"))
      (node (ref "C8") (pin "2") (pinfunction "2_2") (pintype "passive"))
      (node (ref "DA1") (pin "5") (pinfunction "VOUT_5") (pintype "passive"))
      (node (ref "DA2") (pin "6") (pinfunction "VS_6") (pintype "passive"))
      (node (ref "DA3") (pin "6") (pinfunction "VS_6") (pintype "passive"))
      (node (ref "DD1") (pin "1") (pinfunction "VBAT_1") (pintype "passive"))
      (node (ref "DD1") (pin "20") (pinfunction "VREF+_20") (pintype "passive"))
      (node (ref "DD1") (pin "21") (pinfunction "VDDA_21") (pintype "passive"))
      (node (ref "DD1") (pin "23") (pinfunction "VDD_1_23") (pintype "passive"))
      (node (ref "DD1") (pin "35") (pinfunction "VDD_2_35") (pintype "passive"))
      (node (ref "DD1") (pin "48") (pinfunction "VDD_3_48") (pintype "passive"))
      (node (ref "DD10") (pin "5") (pinfunction "VCC_5") (pintype "passive"))
      (node (ref "DD2") (pin "5") (pinfunction "VCC_5") (pintype "passive"))
      (node (ref "DD3") (pin "5") (pinfunction "VCC_5") (pintype "passive"))
      (node (ref "DD4") (pin "5") (pinfunction "VCC_5") (pintype "passive"))
      (node (ref "DD5") (pin "5") (pinfunction "VCC_5") (pintype "passive"))
      (node (ref "DD6") (pin "5") (pinfunction "VCC_5") (pintype "passive"))
      (node (ref "DD7") (pin "5") (pinfunction "VCC_5") (pintype "passive"))
      (node (ref "DD8") (pin "5") (pinfunction "VCC_5") (pintype "passive"))
      (node (ref "DD9") (pin "5") (pinfunction "VCC_5") (pintype "passive"))
      (node (ref "R15") (pin "2") (pinfunction "2_2") (pintype "passive"))
      (node (ref "R16") (pin "2") (pinfunction "2_2") (pintype "passive"))
      (node (ref "R17") (pin "2") (pinfunction "2_2") (pintype "passive"))
      (node (ref "R18") (pin "2") (pinfunction "2_2") (pintype "passive"))
      (node (ref "R19") (pin "2") (pinfunction "2_2") (pintype "passive"))
      (node (ref "R20") (pin "2") (pinfunction "2_2") (pintype "passive"))
      (node (ref "R21") (pin "2") (pinfunction "2_2") (pintype "passive"))
      (node (ref "R22") (pin "2") (pinfunction "2_2") (pintype "passive"))
      (node (ref "R23") (pin "2") (pinfunction "2_2") (pintype "passive"))
      (node (ref "R24") (pin "2") (pinfunction "2_2") (pintype "passive"))
      (node (ref "R25") (pin "2") (pinfunction "2_2") (pintype "passive"))
      (node (ref "SB2") (pin "1") (pinfunction "1_1") (pintype "passive"))
      (node (ref "SB2") (pin "2") (pinfunction "1_2") (pintype "passive"))
      (node (ref "XP2") (pin "1") (pintype "passive"))
    )
    (net (code "40") (name "12V") (class "Default")
      (node (ref "C28") (pin "2") (pinfunction "2_2") (pintype "passive"))
      (node (ref "C29") (pin "2") (pinfunction "2_2") (pintype "passive"))
      (node (ref "DA2") (pin "8") (pinfunction "VBUS_8") (pintype "passive"))
      (node (ref "DA3") (pin "8") (pinfunction "VBUS_8") (pintype "passive"))
      (node (ref "R29") (pin "2") (pinfunction "2_2") (pintype "passive"))
      (node (ref "R30") (pin "2") (pinfunction "2_2") (pintype "passive"))
      (node (ref "R33") (pin "2") (pinfunction "2_2") (pintype "passive"))
      (node (ref "R40") (pin "2") (pinfunction "2_2") (pintype "passive"))
      (node (ref "R47") (pin "2") (pinfunction "2_2") (pintype "passive"))
      (node (ref "R48") (pin "2") (pinfunction "2_2") (pintype "passive"))
      (node (ref "R50") (pin "2") (pinfunction "2_2") (pintype "passive"))
      (node (ref "R52") (pin "2") (pinfunction "2_2") (pintype "passive"))
      (node (ref "VD1") (pin "2") (pinfunction "A_2") (pintype "passive"))
      (node (ref "VT10") (pin "2") (pinfunction "S_2") (pintype "passive"))
      (node (ref "VT19") (pin "2") (pinfunction "S_2") (pintype "passive"))
      (node (ref "VT21") (pin "2") (pinfunction "S_2") (pintype "passive"))
      (node (ref "VT7") (pin "2") (pinfunction "S_2") (pintype "passive"))
      (node (ref "XP8") (pin "1") (pinfunction "1_1") (pintype "passive"))
    )
    (net (code "41") (name "12V PWR") (class "Default")
      (node (ref "C11") (pin "1") (pinfunction "1_1") (pintype "passive"))
      (node (ref "C13") (pin "1") (pinfunction "1_1") (pintype "passive"))
      (node (ref "C9") (pin "1") (pinfunction "+_1") (pintype "passive"))
      (node (ref "L1") (pin "2") (pinfunction "2_2") (pintype "passive"))
      (node (ref "VD3") (pin "1") (pinfunction "K_1") (pintype "passive"))
      (node (ref "VD5") (pin "1") (pinfunction "K_1") (pintype "passive"))
      (node (ref "VD7") (pin "1") (pinfunction "K_1") (pintype "passive"))
      (node (ref "VD9") (pin "1") (pinfunction "K_1") (pintype "passive"))
      (node (ref "VT12") (pin "3") (pinfunction "S_3") (pintype "passive"))
      (node (ref "VT14") (pin "3") (pinfunction "S_3") (pintype "passive"))
      (node (ref "VT16") (pin "3") (pinfunction "S_3") (pintype "passive"))
      (node (ref "VT18") (pin "3") (pinfunction "S_3") (pintype "passive"))
    )
    (net (code "42") (name "GND") (class "Default")
      (node (ref "C1") (pin "2") (pinfunction "2_2") (pintype "passive"))
      (node (ref "C10") (pin "1") (pinfunction "1_1") (pintype "passive"))
      (node (ref "C11") (pin "2") (pinfunction "2_2") (pintype "passive"))
      (node (ref "C12") (pin "1") (pinfunction "1_1") (pintype "passive"))
      (node (ref "C13") (pin "2") (pinfunction "2_2") (pintype "passive"))
      (node (ref "C14") (pin "1") (pinfunction "1_1") (pintype "passive"))
      (node (ref "C15") (pin "1") (pinfunction "1_1") (pintype "passive"))
      (node (ref "C16") (pin "1") (pinfunction "1_1") (pintype "passive"))
      (node (ref "C17") (pin "2") (pinfunction "2_2") (pintype "passive"))
      (node (ref "C18") (pin "2") (pinfunction "2_2") (pintype "passive"))
      (node (ref "C19") (pin "2") (pinfunction "2_2") (pintype "passive"))
      (node (ref "C2") (pin "2") (pinfunction "2_2") (pintype "passive"))
      (node (ref "C20") (pin "2") (pinfunction "2_2") (pintype "passive"))
      (node (ref "C21") (pin "2") (pinfunction "2_2") (pintype "passive"))
      (node (ref "C22") (pin "1") (pinfunction "1_1") (pintype "passive"))
      (node (ref "C23") (pin "1") (pinfunction "1_1") (pintype "passive"))
      (node (ref "C24") (pin "1") (pinfunction "1_1") (pintype "passive"))
      (node (ref "C25") (pin "1") (pinfunction "1_1") (pintype "passive"))
      (node (ref "C26") (pin "1") (pinfunction "1_1") (pintype "passive"))
      (node (ref "C27") (pin "1") (pinfunction "1_1") (pintype "passive"))
      (node (ref "C28") (pin "1") (pinfunction "1_1") (pintype "passive"))
      (node (ref "C29") (pin "1") (pinfunction "1_1") (pintype "passive"))
      (node (ref "C3") (pin "1") (pinfunction "1_1") (pintype "passive"))
      (node (ref "C32") (pin "2") (pinfunction "2_2") (pintype "passive"))
      (node (ref "C33") (pin "2") (pinfunction "2_2") (pintype "passive"))
      (node (ref "C34") (pin "2") (pinfunction "2_2") (pintype "passive"))
      (node (ref "C35") (pin "2") (pinfunction "2_2") (pintype "passive"))
      (node (ref "C4") (pin "2") (pinfunction "-_2") (pintype "passive"))
      (node (ref "C5") (pin "1") (pinfunction "1_1") (pintype "passive"))
      (node (ref "C6") (pin "1") (pinfunction "1_1") (pintype "passive"))
      (node (ref "C7") (pin "1") (pinfunction "1_1") (pintype "passive"))
      (node (ref "C8") (pin "1") (pinfunction "1_1") (pintype "passive"))
      (node (ref "C9") (pin "2") (pinfunction "-_2") (pintype "passive"))
      (node (ref "DA1") (pin "2") (pinfunction "GND_2") (pintype "passive"))
      (node (ref "DA2") (pin "1") (pinfunction "A1_1") (pintype "passive"))
      (node (ref "DA2") (pin "2") (pinfunction "A0_2") (pintype "passive"))
      (node (ref "DA2") (pin "7") (pinfunction "GND_7") (pintype "passive"))
      (node (ref "DA3") (pin "1") (pinfunction "A1_1") (pintype "passive"))
      (node (ref "DA3") (pin "2") (pinfunction "A0_2") (pintype "passive"))
      (node (ref "DA3") (pin "7") (pinfunction "GND_7") (pintype "passive"))
      (node (ref "DD1") (pin "49") (pinfunction "EP_49") (pintype "passive"))
      (node (ref "DD10") (pin "2") (pinfunction "GND_2") (pintype "passive"))
      (node (ref "DD2") (pin "2") (pinfunction "GND_2") (pintype "passive"))
      (node (ref "DD3") (pin "2") (pinfunction "GND_2") (pintype "passive"))
      (node (ref "DD4") (pin "2") (pinfunction "GND_2") (pintype "passive"))
      (node (ref "DD5") (pin "2") (pinfunction "GND_2") (pintype "passive"))
      (node (ref "DD6") (pin "2") (pinfunction "GND_2") (pintype "passive"))
      (node (ref "DD7") (pin "2") (pinfunction "GND_2") (pintype "passive"))
      (node (ref "DD8") (pin "2") (pinfunction "GND_2") (pintype "passive"))
      (node (ref "DD9") (pin "2") (pinfunction "GND_2") (pintype "passive"))
      (node (ref "R1") (pin "1") (pinfunction "1_1") (pintype "passive"))
      (node (ref "R2") (pin "1") (pinfunction "1_1") (pintype "passive"))
      (node (ref "R26") (pin "1") (pinfunction "1_1") (pintype "passive"))
      (node (ref "R27") (pin "1") (pinfunction "1_1") (pintype "passive"))
      (node (ref "R28") (pin "1") (pinfunction "1_1") (pintype "passive"))
      (node (ref "R31") (pin "1") (pinfunction "1_1") (pintype "passive"))
      (node (ref "R34") (pin "1") (pinfunction "1_1") (pintype "passive"))
      (node (ref "R35") (pin "1") (pinfunction "1_1") (pintype "passive"))
      (node (ref "R36") (pin "1") (pinfunction "1_1") (pintype "passive"))
      (node (ref "R37") (pin "1") (pinfunction "1_1") (pintype "passive"))
      (node (ref "R38") (pin "1") (pinfunction "1_1") (pintype "passive"))
      (node (ref "R43") (pin "1") (pinfunction "1_1") (pintype "passive"))
      (node (ref "R44") (pin "1") (pinfunction "1_1") (pintype "passive"))
      (node (ref "R49") (pin "1") (pinfunction "1_1") (pintype "passive"))
      (node (ref "R5") (pin "1") (pinfunction "1_1") (pintype "passive"))
      (node (ref "R51") (pin "1") (pinfunction "1_1") (pintype "passive"))
      (node (ref "R53") (pin "1") (pinfunction "1_1") (pintype "passive"))
      (node (ref "R54") (pin "1") (pinfunction "1_1") (pintype "passive"))
      (node (ref "R6") (pin "1") (pinfunction "1_1") (pintype "passive"))
      (node (ref "SB1") (pin "1") (pinfunction "1_1") (pintype "passive"))
      (node (ref "SB1") (pin "2") (pinfunction "1_2") (pintype "passive"))
      (node (ref "VT1") (pin "2") (pinfunction "S_2") (pintype "passive"))
      (node (ref "VT2") (pin "2") (pinfunction "S_2") (pintype "passive"))
      (node (ref "VT20") (pin "2") (pinfunction "S_2") (pintype "passive"))
      (node (ref "VT22") (pin "2") (pinfunction "S_2") (pintype "passive"))
      (node (ref "VT23") (pin "2") (pinfunction "S_2") (pintype "passive"))
      (node (ref "VT24") (pin "2") (pinfunction "S_2") (pintype "passive"))
      (node (ref "VT5") (pin "2") (pinfunction "S_2") (pintype "passive"))
      (node (ref "VT6") (pin "2") (pinfunction "S_2") (pintype "passive"))
      (node (ref "VT8") (pin "2") (pinfunction "S_2") (pintype "passive"))
      (node (ref "VT9") (pin "2") (pinfunction "S_2") (pintype "passive"))
      (node (ref "XP1") (pin "2") (pinfunction "N_2") (pintype "passive"))
      (node (ref "XP2") (pin "6") (pintype "passive"))
      (node (ref "XP3") (pin "2") (pintype "passive"))
      (node (ref "XP4") (pin "2") (pintype "passive"))
      (node (ref "XP5") (pin "2") (pintype "passive"))
      (node (ref "XP6") (pin "2") (pintype "passive"))
      (node (ref "XP7") (pin "3") (pinfunction "3_3") (pintype "passive"))
      (node (ref "XP8") (pin "15") (pinfunction "15_15") (pintype "passive"))
      (node (ref "XP8") (pin "9") (pinfunction "9_9") (pintype "passive"))
      (node (ref "XS1") (pin "3") (pinfunction "3_3") (pintype "passive"))
      (node (ref "XS1") (pin "9") (pinfunction "9_9") (pintype "passive"))
      (node (ref "XS2") (pin "3") (pinfunction "3_3") (pintype "passive"))
    )
    (net (code "43") (name "Net-(DA1-ADJ{slash}BYP)") (class "Default")
      (node (ref "C15") (pin "2") (pinfunction "2_2") (pintype "passive"))
      (node (ref "DA1") (pin "4") (pinfunction "ADJ/BYP_4") (pintype "passive"))
    )
    (net (code "44") (name "Net-(DA2-ALERT)") (class "Default")
      (node (ref "DA2") (pin "3") (pinfunction "ALERT_3") (pintype "passive"))
      (node (ref "R24") (pin "1") (pinfunction "1_1") (pintype "passive"))
    )
    (net (code "45") (name "Net-(DA2-VIN+)") (class "Default")
      (node (ref "C30") (pin "2") (pinfunction "2_2") (pintype "passive"))
      (node (ref "DA2") (pin "10") (pinfunction "VIN+_10") (pintype "passive"))
      (node (ref "R32") (pin "2") (pinfunction "2_2") (pintype "passive"))
    )
    (net (code "46") (name "Net-(DA2-VIN-)") (class "Default")
      (node (ref "C30") (pin "1") (pinfunction "1_1") (pintype "passive"))
      (node (ref "DA2") (pin "9") (pinfunction "VIN-_9") (pintype "passive"))
      (node (ref "R35") (pin "2") (pinfunction "2_2") (pintype "passive"))
    )
    (net (code "47") (name "Net-(DA3-ALERT)") (class "Default")
      (node (ref "DA3") (pin "3") (pinfunction "ALERT_3") (pintype "passive"))
      (node (ref "R25") (pin "1") (pinfunction "1_1") (pintype "passive"))
    )
    (net (code "48") (name "Net-(DA3-VIN+)") (class "Default")
      (node (ref "C31") (pin "2") (pinfunction "2_2") (pintype "passive"))
      (node (ref "DA3") (pin "10") (pinfunction "VIN+_10") (pintype "passive"))
      (node (ref "R39") (pin "2") (pinfunction "2_2") (pintype "passive"))
    )
    (net (code "49") (name "Net-(DA3-VIN-)") (class "Default")
      (node (ref "C31") (pin "1") (pinfunction "1_1") (pintype "passive"))
      (node (ref "DA3") (pin "9") (pinfunction "VIN-_9") (pintype "passive"))
      (node (ref "R38") (pin "2") (pinfunction "2_2") (pintype "passive"))
    )
    (net (code "50") (name "Net-(DD1-PA11)") (class "Default")
      (node (ref "DD1") (pin "33") (pinfunction "PA11_33") (pintype "passive"))
      (node (ref "R4") (pin "1") (pinfunction "1_1") (pintype "passive"))
    )
    (net (code "51") (name "Net-(DD1-PA12)") (class "Default")
      (node (ref "DD1") (pin "34") (pinfunction "PA12_34") (pintype "passive"))
      (node (ref "R3") (pin "1") (pinfunction "1_1") (pintype "passive"))
    )
    (net (code "52") (name "Net-(DD1-PA13)") (class "Default")
      (node (ref "DD1") (pin "36") (pinfunction "PA13_36") (pintype "passive"))
      (node (ref "XP2") (pin "4") (pintype "passive"))
    )
    (net (code "53") (name "Net-(DD1-PA14)") (class "Default")
      (node (ref "DD1") (pin "37") (pinfunction "PA14_37") (pintype "passive"))
      (node (ref "XP2") (pin "3") (pintype "passive"))
    )
    (net (code "54") (name "Net-(DD1-PB3)") (class "Default")
      (node (ref "DD1") (pin "41") (pinfunction "PB3_41") (pintype "passive"))
      (node (ref "DD6") (pin "6") (pinfunction "1Y_6") (pintype "passive"))
    )
    (net (code "55") (name "Net-(DD1-PB4)") (class "Default")
      (node (ref "DD1") (pin "42") (pinfunction "PB4_42") (pintype "passive"))
      (node (ref "DD5") (pin "4") (pinfunction "2Y_4") (pintype "passive"))
    )
    (net (code "56") (name "Net-(DD1-PB5)") (class "Default")
      (node (ref "DD1") (pin "43") (pinfunction "PB5_43") (pintype "passive"))
      (node (ref "DD5") (pin "6") (pinfunction "1Y_6") (pintype "passive"))
    )
    (net (code "57") (name "Net-(DD1-PB6)") (class "Default")
      (node (ref "DD1") (pin "44") (pinfunction "PB6_44") (pintype "passive"))
      (node (ref "DD4") (pin "4") (pinfunction "2Y_4") (pintype "passive"))
    )
    (net (code "58") (name "Net-(DD1-PB7)") (class "Default")
      (node (ref "DD1") (pin "45") (pinfunction "PB7_45") (pintype "passive"))
      (node (ref "DD4") (pin "6") (pinfunction "1Y_6") (pintype "passive"))
    )
    (net (code "59") (name "Net-(DD1-PB10)") (class "Default")
      (node (ref "DD1") (pin "22") (pinfunction "PB10_22") (pintype "passive"))
      (node (ref "HL1") (pin "2") (pinfunction "A_2") (pintype "passive"))
    )
    (net (code "60") (name "Net-(DD1-PF0-OSC_IN)") (class "Default")
      (node (ref "BQ1") (pin "2") (pinfunction "2_2") (pintype "passive"))
      (node (ref "C2") (pin "1") (pinfunction "1_1") (pintype "passive"))
      (node (ref "DD1") (pin "5") (pinfunction "PF0-OSC_IN_5") (pintype "passive"))
    )
    (net (code "61") (name "Net-(DD1-PF1-OSC_OUT)") (class "Default")
      (node (ref "BQ1") (pin "1") (pinfunction "1_1") (pintype "passive"))
      (node (ref "C1") (pin "1") (pinfunction "1_1") (pintype "passive"))
      (node (ref "DD1") (pin "6") (pinfunction "PF1-OSC_OUT_6") (pintype "passive"))
    )
    (net (code "62") (name "Net-(DD1-PG10-NRST)") (class "Default")
      (node (ref "C3") (pin "2") (pinfunction "2_2") (pintype "passive"))
      (node (ref "DD1") (pin "7") (pinfunction "PG10-NRST_7") (pintype "passive"))
      (node (ref "SB1") (pin "3") (pinfunction "2_3") (pintype "passive"))
      (node (ref "SB1") (pin "4") (pinfunction "2_4") (pintype "passive"))
      (node (ref "XP2") (pin "2") (pintype "passive"))
    )
    (net (code "63") (name "Net-(DD2-1Y)") (class "Default")
      (node (ref "DD2") (pin "6") (pinfunction "1Y_6") (pintype "passive"))
      (node (ref "R9") (pin "1") (pinfunction "1_1") (pintype "passive"))
    )
    (net (code "64") (name "Net-(DD2-2Y)") (class "Default")
      (node (ref "DD2") (pin "4") (pinfunction "2Y_4") (pintype "passive"))
      (node (ref "R10") (pin "1") (pinfunction "1_1") (pintype "passive"))
    )
    (net (code "65") (name "Net-(DD3-1Y)") (class "Default")
      (node (ref "DD3") (pin "6") (pinfunction "1Y_6") (pintype "passive"))
      (node (ref "R11") (pin "1") (pinfunction "1_1") (pintype "passive"))
    )
    (net (code "66") (name "Net-(DD3-2Y)") (class "Default")
      (node (ref "DD3") (pin "4") (pinfunction "2Y_4") (pintype "passive"))
      (node (ref "R12") (pin "1") (pinfunction "1_1") (pintype "passive"))
    )
    (net (code "67") (name "Net-(DD6-1A)") (class "Default")
      (node (ref "DD6") (pin "1") (pinfunction "1A_1") (pintype "passive"))
      (node (ref "R23") (pin "1") (pinfunction "1_1") (pintype "passive"))
      (node (ref "R26") (pin "2") (pinfunction "2_2") (pintype "passive"))
    )
    (net (code "68") (name "Net-(HL1-K)") (class "Default")
      (node (ref "HL1") (pin "1") (pinfunction "K_1") (pintype "passive"))
      (node (ref "R1") (pin "2") (pinfunction "2_2") (pintype "passive"))
    )
    (net (code "69") (name "Net-(R9-Pad2)") (class "Default")
      (node (ref "R9") (pin "2") (pinfunction "2_2") (pintype "passive"))
      (node (ref "XP3") (pin "1") (pintype "passive"))
    )
    (net (code "70") (name "Net-(R10-Pad2)") (class "Default")
      (node (ref "R10") (pin "2") (pinfunction "2_2") (pintype "passive"))
      (node (ref "XP4") (pin "1") (pintype "passive"))
    )
    (net (code "71") (name "Net-(R11-Pad2)") (class "Default")
      (node (ref "R11") (pin "2") (pinfunction "2_2") (pintype "passive"))
      (node (ref "XP5") (pin "1") (pintype "passive"))
    )
    (net (code "72") (name "Net-(R12-Pad2)") (class "Default")
      (node (ref "R12") (pin "2") (pinfunction "2_2") (pintype "passive"))
      (node (ref "XP6") (pin "1") (pintype "passive"))
    )
    (net (code "73") (name "Net-(VD2-A)") (class "Default")
      (node (ref "VD2") (pin "2") (pinfunction "A_2") (pintype "passive"))
      (node (ref "XS1") (pin "8") (pinfunction "8_8") (pintype "passive"))
    )
    (net (code "74") (name "Net-(VD4-A)") (class "Default")
      (node (ref "R32") (pin "1") (pinfunction "1_1") (pintype "passive"))
      (node (ref "R43") (pin "2") (pinfunction "2_2") (pintype "passive"))
      (node (ref "VD4") (pin "2") (pinfunction "A_2") (pintype "passive"))
      (node (ref "VD8") (pin "2") (pinfunction "A_2") (pintype "passive"))
      (node (ref "VT11") (pin "3") (pinfunction "SOURCE_3") (pintype "passive"))
      (node (ref "VT15") (pin "3") (pinfunction "SOURCE_3") (pintype "passive"))
    )
    (net (code "75") (name "Net-(VD10-A)") (class "Default")
      (node (ref "R39") (pin "1") (pinfunction "1_1") (pintype "passive"))
      (node (ref "R44") (pin "2") (pinfunction "2_2") (pintype "passive"))
      (node (ref "VD10") (pin "2") (pinfunction "A_2") (pintype "passive"))
      (node (ref "VD6") (pin "2") (pinfunction "A_2") (pintype "passive"))
      (node (ref "VT13") (pin "3") (pinfunction "SOURCE_3") (pintype "passive"))
      (node (ref "VT17") (pin "3") (pinfunction "SOURCE_3") (pintype "passive"))
    )
    (net (code "76") (name "Net-(VT1-D)") (class "Default")
      (node (ref "R7") (pin "1") (pinfunction "1_1") (pintype "passive"))
      (node (ref "VT1") (pin "3") (pinfunction "D_3") (pintype "passive"))
      (node (ref "VT3") (pin "1") (pinfunction "G_1") (pintype "passive"))
    )
    (net (code "77") (name "Net-(VT2-D)") (class "Default")
      (node (ref "R8") (pin "1") (pinfunction "1_1") (pintype "passive"))
      (node (ref "VT2") (pin "3") (pinfunction "D_3") (pintype "passive"))
      (node (ref "VT4") (pin "1") (pinfunction "G_1") (pintype "passive"))
    )
    (net (code "78") (name "Net-(VT3-D)") (class "Default")
      (node (ref "R13") (pin "2") (pinfunction "2_2") (pintype "passive"))
      (node (ref "VT3") (pin "3") (pinfunction "D_3") (pintype "passive"))
    )
    (net (code "79") (name "Net-(VT4-D)") (class "Default")
      (node (ref "R14") (pin "2") (pinfunction "2_2") (pintype "passive"))
      (node (ref "VT4") (pin "3") (pinfunction "D_3") (pintype "passive"))
    )
    (net (code "80") (name "Net-(VT5-D)") (class "Default")
      (node (ref "R30") (pin "1") (pinfunction "1_1") (pintype "passive"))
      (node (ref "VT5") (pin "3") (pinfunction "D_3") (pintype "passive"))
      (node (ref "VT7") (pin "1") (pinfunction "G_1") (pintype "passive"))
    )
    (net (code "81") (name "Net-(VT7-D)") (class "Default")
      (node (ref "R41") (pin "1") (pinfunction "1_1") (pintype "passive"))
      (node (ref "VT7") (pin "3") (pinfunction "D_3") (pintype "passive"))
    )
    (net (code "82") (name "Net-(VT10-D)") (class "Default")
      (node (ref "R42") (pin "1") (pinfunction "1_1") (pintype "passive"))
      (node (ref "VT10") (pin "3") (pinfunction "D_3") (pintype "passive"))
    )
    (net (code "83") (name "Net-(VT10-G)") (class "Default")
      (node (ref "R40") (pin "1") (pinfunction "1_1") (pintype "passive"))
      (node (ref "VT10") (pin "1") (pinfunction "G_1") (pintype "passive"))
      (node (ref "VT9") (pin "3") (pinfunction "D_3") (pintype "passive"))
    )
    (net (code "84") (name "Net-(VT11-GATE)") (class "Default")
      (node (ref "R41") (pin "2") (pinfunction "2_2") (pintype "passive"))
      (node (ref "VT11") (pin "1") (pinfunction "GATE_1") (pintype "passive"))
    )
    (net (code "85") (name "Net-(VT12-G)") (class "Default")
      (node (ref "R33") (pin "1") (pinfunction "1_1") (pintype "passive"))
      (node (ref "VT12") (pin "1") (pinfunction "G_1") (pintype "passive"))
      (node (ref "VT6") (pin "3") (pinfunction "D_3") (pintype "passive"))
    )
    (net (code "86") (name "Net-(VT13-GATE)") (class "Default")
      (node (ref "R42") (pin "2") (pinfunction "2_2") (pintype "passive"))
      (node (ref "VT13") (pin "1") (pinfunction "GATE_1") (pintype "passive"))
    )
    (net (code "87") (name "Net-(VT14-G)") (class "Default")
      (node (ref "R29") (pin "1") (pinfunction "1_1") (pintype "passive"))
      (node (ref "VT14") (pin "1") (pinfunction "G_1") (pintype "passive"))
      (node (ref "VT8") (pin "3") (pinfunction "D_3") (pintype "passive"))
    )
    (net (code "88") (name "Net-(VT15-GATE)") (class "Default")
      (node (ref "R45") (pin "2") (pinfunction "2_2") (pintype "passive"))
      (node (ref "VT15") (pin "1") (pinfunction "GATE_1") (pintype "passive"))
    )
    (net (code "89") (name "Net-(VT16-G)") (class "Default")
      (node (ref "R47") (pin "1") (pinfunction "1_1") (pintype "passive"))
      (node (ref "VT16") (pin "1") (pinfunction "G_1") (pintype "passive"))
      (node (ref "VT23") (pin "3") (pinfunction "D_3") (pintype "passive"))
    )
    (net (code "90") (name "Net-(VT17-GATE)") (class "Default")
      (node (ref "R46") (pin "2") (pinfunction "2_2") (pintype "passive"))
      (node (ref "VT17") (pin "1") (pinfunction "GATE_1") (pintype "passive"))
    )
    (net (code "91") (name "Net-(VT18-G)") (class "Default")
      (node (ref "R50") (pin "1") (pinfunction "1_1") (pintype "passive"))
      (node (ref "VT18") (pin "1") (pinfunction "G_1") (pintype "passive"))
      (node (ref "VT24") (pin "3") (pinfunction "D_3") (pintype "passive"))
    )
    (net (code "92") (name "Net-(VT19-D)") (class "Default")
      (node (ref "R45") (pin "1") (pinfunction "1_1") (pintype "passive"))
      (node (ref "VT19") (pin "3") (pinfunction "D_3") (pintype "passive"))
    )
    (net (code "93") (name "Net-(VT19-G)") (class "Default")
      (node (ref "R48") (pin "1") (pinfunction "1_1") (pintype "passive"))
      (node (ref "VT19") (pin "1") (pinfunction "G_1") (pintype "passive"))
      (node (ref "VT20") (pin "3") (pinfunction "D_3") (pintype "passive"))
    )
    (net (code "94") (name "Net-(VT21-D)") (class "Default")
      (node (ref "R46") (pin "1") (pinfunction "1_1") (pintype "passive"))
      (node (ref "VT21") (pin "3") (pinfunction "D_3") (pintype "passive"))
    )
    (net (code "95") (name "Net-(VT21-G)") (class "Default")
      (node (ref "R52") (pin "1") (pinfunction "1_1") (pintype "passive"))
      (node (ref "VT21") (pin "1") (pinfunction "G_1") (pintype "passive"))
      (node (ref "VT22") (pin "3") (pinfunction "D_3") (pintype "passive"))
    )
    (net (code "96") (name "Net-(XP1-P)") (class "Default")
      (node (ref "L1") (pin "1") (pinfunction "1_1") (pintype "passive"))
      (node (ref "XP1") (pin "1") (pinfunction "P_1") (pintype "passive"))
    )
    (net (code "97") (name "Vcc") (class "Default")
      (node (ref "C4") (pin "1") (pinfunction "+_1") (pintype "passive"))
      (node (ref "C7") (pin "2") (pinfunction "2_2") (pintype "passive"))
      (node (ref "DA1") (pin "1") (pinfunction "VIN_1") (pintype "passive"))
      (node (ref "DA1") (pin "3") (pinfunction "EN_3") (pintype "passive"))
      (node (ref "R7") (pin "2") (pinfunction "2_2") (pintype "passive"))
      (node (ref "R8") (pin "2") (pinfunction "2_2") (pintype "passive"))
      (node (ref "VD1") (pin "1") (pinfunction "K_1") (pintype "passive"))
      (node (ref "VD2") (pin "1") (pinfunction "K_1") (pintype "passive"))
      (node (ref "VT3") (pin "2") (pinfunction "S_2") (pintype "passive"))
      (node (ref "VT4") (pin "2") (pinfunction "S_2") (pintype "passive"))
    )
    (net (code "98") (name "unconnected-(DD1-PA5-Pad13)") (class "Default")
      (node (ref "DD1") (pin "13") (pinfunction "PA5_13") (pintype "passive"))
    )
    (net (code "99") (name "unconnected-(DD1-PA7-Pad15)") (class "Default")
      (node (ref "DD1") (pin "15") (pinfunction "PA7_15") (pintype "passive"))
    )
    (net (code "100") (name "unconnected-(DD1-PB0-Pad17)") (class "Default")
      (node (ref "DD1") (pin "17") (pinfunction "PB0_17") (pintype "passive"))
    )
    (net (code "101") (name "unconnected-(DD1-PB1-Pad18)") (class "Default")
      (node (ref "DD1") (pin "18") (pinfunction "PB1_18") (pintype "passive"))
    )
    (net (code "102") (name "unconnected-(DD1-PB2-Pad19)") (class "Default")
      (node (ref "DD1") (pin "19") (pinfunction "PB2_19") (pintype "passive"))
    )
    (net (code "103") (name "unconnected-(DD1-PB11-Pad24)") (class "Default")
      (node (ref "DD1") (pin "24") (pinfunction "PB11_24") (pintype "passive"))
    )
    (net (code "104") (name "unconnected-(DD1-PC6-Pad29)") (class "Default")
      (node (ref "DD1") (pin "29") (pinfunction "PC6_29") (pintype "passive"))
    )
    (net (code "105") (name "unconnected-(DD1-PC10-Pad39)") (class "Default")
      (node (ref "DD1") (pin "39") (pinfunction "PC10_39") (pintype "passive"))
    )
    (net (code "106") (name "unconnected-(DD1-PC11-Pad40)") (class "Default")
      (node (ref "DD1") (pin "40") (pinfunction "PC11_40") (pintype "passive"))
    )
    (net (code "107") (name "unconnected-(DD1-PC13-Pad2)") (class "Default")
      (node (ref "DD1") (pin "2") (pinfunction "PC13_2") (pintype "passive"))
    )
    (net (code "108") (name "unconnected-(DD1-PC14-OSC32_IN-Pad3)") (class "Default")
      (node (ref "DD1") (pin "3") (pinfunction "PC14-OSC32_IN_3") (pintype "passive"))
    )
    (net (code "109") (name "unconnected-(DD1-PC15-OSC32_OUT-Pad4)") (class "Default")
      (node (ref "DD1") (pin "4") (pinfunction "PC15-OSC32_OUT_4") (pintype "passive"))
    )
    (net (code "110") (name "unconnected-(DD6-2A-Pad3)") (class "Default")
      (node (ref "DD6") (pin "3") (pinfunction "2A_3") (pintype "passive"))
    )
    (net (code "111") (name "unconnected-(DD6-2Y-Pad4)") (class "Default")
      (node (ref "DD6") (pin "4") (pinfunction "2Y_4") (pintype "passive"))
    )
    (net (code "112") (name "unconnected-(XP1-SHIELD-PadSH1)") (class "Default")
      (node (ref "XP1") (pin "SH1") (pinfunction "SHIELD_SH1") (pintype "passive"))
    )
    (net (code "113") (name "unconnected-(XP1-SHIELD-PadSH2)") (class "Default")
      (node (ref "XP1") (pin "SH2") (pinfunction "SHIELD_SH2") (pintype "passive"))
    )
    (net (code "114") (name "unconnected-(XP2-Pad5)") (class "Default")
      (node (ref "XP2") (pin "5") (pintype "passive"))
    )
    (net (code "115") (name "unconnected-(XP7-MH1-Pad4)") (class "Default")
      (node (ref "XP7") (pin "4") (pinfunction "MH1_4") (pintype "passive"))
    )
    (net (code "116") (name "unconnected-(XP7-MH2-Pad5)") (class "Default")
      (node (ref "XP7") (pin "5") (pinfunction "MH2_5") (pintype "passive"))
    )
    (net (code "117") (name "unconnected-(XP8-Pad2)") (class "Default")
      (node (ref "XP8") (pin "2") (pinfunction "2_2") (pintype "passive"))
    )
    (net (code "118") (name "unconnected-(XP8-Pad5)") (class "Default")
      (node (ref "XP8") (pin "5") (pinfunction "5_5") (pintype "passive"))
    )
    (net (code "119") (name "unconnected-(XP8-Pad10)") (class "Default")
      (node (ref "XP8") (pin "10") (pinfunction "10_10") (pintype "passive"))
    )
    (net (code "120") (name "unconnected-(XP8-Pad11)") (class "Default")
      (node (ref "XP8") (pin "11") (pinfunction "11_11") (pintype "passive"))
    )
    (net (code "121") (name "unconnected-(XP8-Pad12)") (class "Default")
      (node (ref "XP8") (pin "12") (pinfunction "12_12") (pintype "passive"))
    )
    (net (code "122") (name "unconnected-(XP8-Pad13)") (class "Default")
      (node (ref "XP8") (pin "13") (pinfunction "13_13") (pintype "passive"))
    )
    (net (code "123") (name "unconnected-(XP8-Pad14)") (class "Default")
      (node (ref "XP8") (pin "14") (pinfunction "14_14") (pintype "passive"))
    )
    (net (code "124") (name "unconnected-(XS1-Pad7)") (class "Default")
      (node (ref "XS1") (pin "7") (pinfunction "7_7") (pintype "passive"))
    )
    (net (code "125") (name "unconnected-(XS1-SHIELD-PadSH1)") (class "Default")
      (node (ref "XS1") (pin "SH1") (pinfunction "SHIELD_SH1") (pintype "passive"))
    )
    (net (code "126") (name "unconnected-(XS1-SHIELD-PadSH2)") (class "Default")
      (node (ref "XS1") (pin "SH2") (pinfunction "SHIELD_SH2") (pintype "passive"))
    )
    (net (code "127") (name "unconnected-(XS2-MH1-Pad4)") (class "Default")
      (node (ref "XS2") (pin "4") (pinfunction "MH1_4") (pintype "passive"))
    )
    (net (code "128") (name "unconnected-(XS2-MH2-Pad5)") (class "Default")
      (node (ref "XS2") (pin "5") (pinfunction "MH2_5") (pintype "passive"))
    )
  )
)
